# triger.net
KiCad netlist of a schematic drawn in Altium Designer
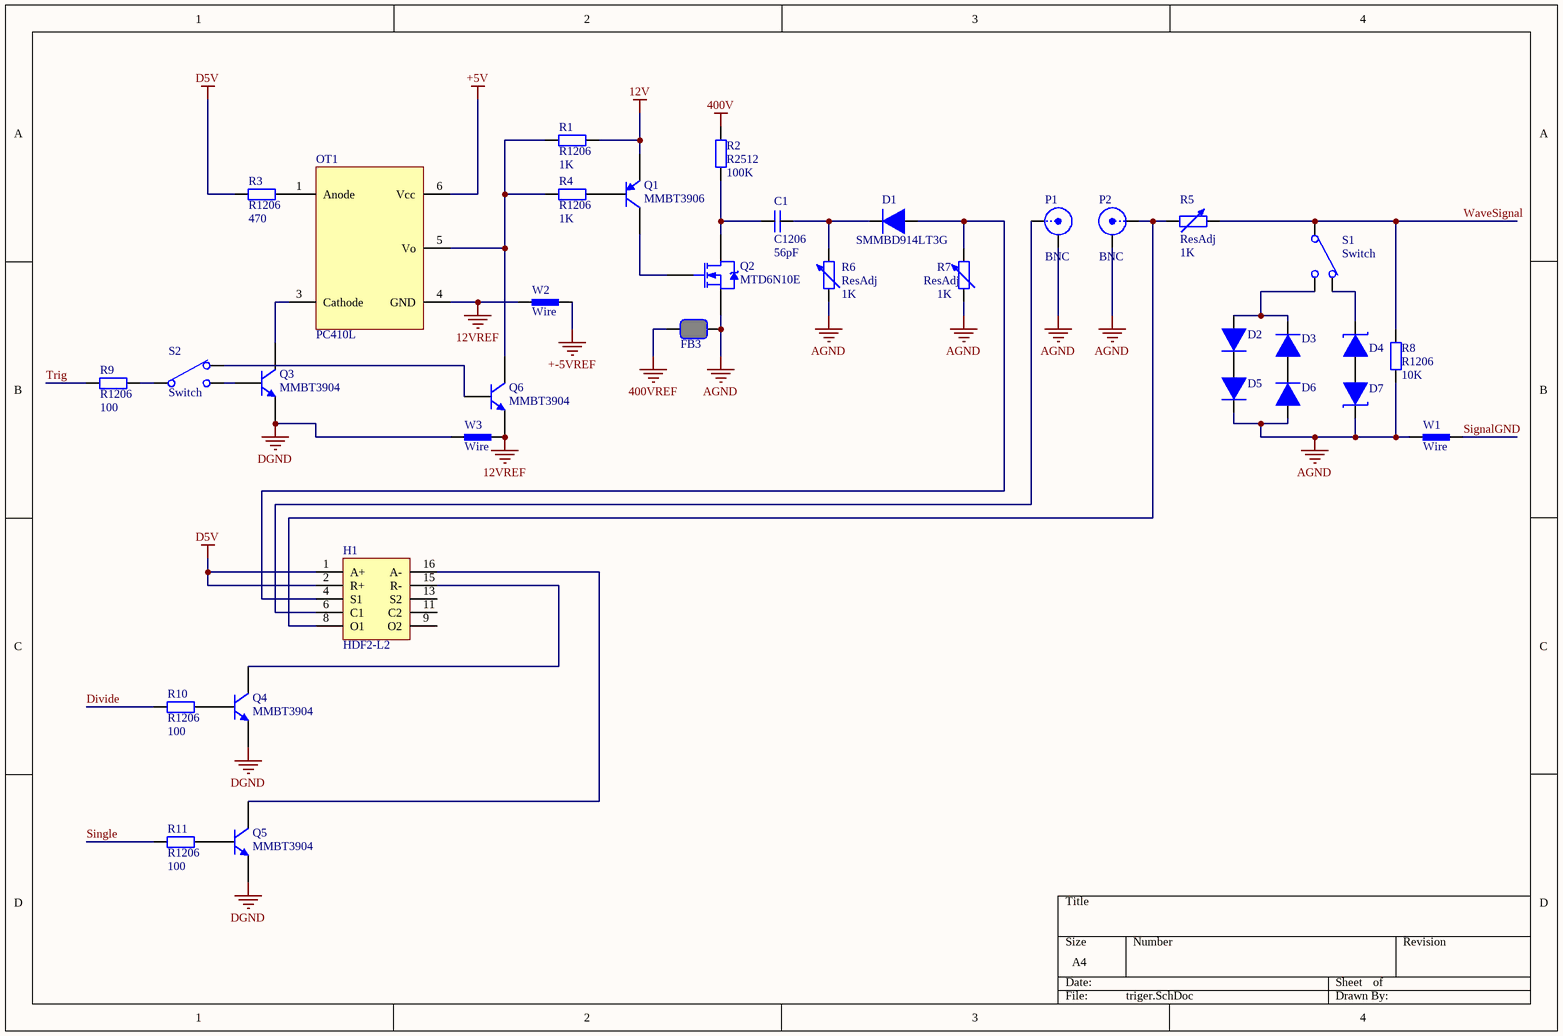
[diagram p0: triger.SchDoc]

(export (version "E")
  (design (tool "Eeschema 10.0.6"))
  (components
    (comp (ref "C1")
      (value "C1206")
      (footprint "1206")
      (description "Capacitor, 1206")
      (fields (field (name "ALTIUM_VALUE") "56pF"))
      (libsource (lib "UFDLib") (part "C1206"))
    )
    (comp (ref "D1")
      (value "SMMBD914LT3G")
      (footprint "SMMBD914LT3G")
      (description "Switching Diode")
      (libsource (lib "UFDLib") (part "SMMBD914LT3G"))
    )
    (comp (ref "D2")
      (value "SMMBD914LT3G")
      (footprint "SMMBD914LT3G")
      (description "Switching Diode")
      (libsource (lib "UFDLib") (part "SMMBD914LT3G"))
    )
    (comp (ref "D3")
      (value "SMMBD914LT3G")
      (footprint "SMMBD914LT3G")
      (description "Switching Diode")
      (libsource (lib "UFDLib") (part "SMMBD914LT3G"))
    )
    (comp (ref "D4")
      (value "ZMM2V4")
      (footprint "DIODE1206")
      (description "Voltage Stabilizing Diode, 2.4V")
      (libsource (lib "UFDLib") (part "ZMM2V4"))
    )
    (comp (ref "D5")
      (value "SMMBD914LT3G")
      (footprint "SMMBD914LT3G")
      (description "Switching Diode")
      (libsource (lib "UFDLib") (part "SMMBD914LT3G"))
    )
    (comp (ref "D6")
      (value "SMMBD914LT3G")
      (footprint "SMMBD914LT3G")
      (description "Switching Diode")
      (libsource (lib "UFDLib") (part "SMMBD914LT3G"))
    )
    (comp (ref "D7")
      (value "ZMM2V4")
      (footprint "DIODE1206")
      (description "Voltage Stabilizing Diode, 2.4V")
      (libsource (lib "UFDLib") (part "ZMM2V4"))
    )
    (comp (ref "FB3")
      (value "FB0805")
      (footprint "0805")
      (description "Chip Bead, 0805")
      (libsource (lib "UFDLib") (part "FB0805"))
    )
    (comp (ref "H1")
      (value "HDF2-L2")
      (footprint "RELAY-HFD2-L2")
      (description "Relay, HDF2-XX-XX-L2-XX")
      (libsource (lib "UFDLib") (part "Relay-HDF2-L2"))
    )
    (comp (ref "OT1") (value "PC410L") (footprint "SOP5") (libsource (lib "UFDLib") (part "PC410L")))
    (comp (ref "P1")
      (value "BNC")
      (footprint "BNC_RA CON")
      (description "BNC Elbow Connector")
      (fields (field (name "PUBLISHER") "Altium Limited"))
      (libsource (lib "Miscellaneous Connectors") (part "BNC"))
    )
    (comp (ref "P2")
      (value "BNC")
      (footprint "BNC_RA CON")
      (description "BNC Elbow Connector")
      (fields (field (name "PUBLISHER") "Altium Limited"))
      (libsource (lib "Miscellaneous Connectors") (part "BNC"))
    )
    (comp (ref "Q1")
      (value "MMBT3906")
      (footprint "SOT23_M")
      (description "PNP Switching Transistor")
      (fields (field (name "PUBLISHER") "Altium Limited"))
      (libsource (lib "Philips Discrete BJT - Low Power") (part "MMBT3906"))
    )
    (comp (ref "Q2")
      (value "MTD6N10E")
      (footprint "369A-13")
      (description "TMOS E-FET Power Field Effect Transistor DPAK for Surface Mount")
      (fields (field (name "PUBLISHER") "Altium Limited"))
      (libsource (lib "Motorola Discrete MOSFET") (part "MTD6N10E"))
    )
    (comp (ref "Q3")
      (value "MMBT3904")
      (footprint "SOT23_M")
      (description "NPN Switching Transistor")
      (fields (field (name "PUBLISHER") "Altium Limited"))
      (libsource (lib "Philips Discrete BJT - Low Power") (part "MMBT3904"))
    )
    (comp (ref "Q4")
      (value "MMBT3904")
      (footprint "SOT23_M")
      (description "NPN Switching Transistor")
      (fields (field (name "PUBLISHER") "Altium Limited"))
      (libsource (lib "Philips Discrete BJT - Low Power") (part "MMBT3904"))
    )
    (comp (ref "Q5")
      (value "MMBT3904")
      (footprint "SOT23_M")
      (description "NPN Switching Transistor")
      (fields (field (name "PUBLISHER") "Altium Limited"))
      (libsource (lib "Philips Discrete BJT - Low Power") (part "MMBT3904"))
    )
    (comp (ref "Q6")
      (value "MMBT3904")
      (footprint "SOT23_M")
      (description "NPN Switching Transistor")
      (fields (field (name "PUBLISHER") "Altium Limited"))
      (libsource (lib "Philips Discrete BJT - Low Power") (part "MMBT3904"))
    )
    (comp (ref "R1")
      (value "R1206")
      (footprint "1206")
      (description "Resistor, 1206, 1/4W")
      (fields (field (name "ALTIUM_VALUE") "1K"))
      (libsource (lib "UFDLib") (part "R1206"))
    )
    (comp (ref "R2")
      (value "R2512")
      (footprint "2512")
      (description "Resistor, 2512, 1W")
      (fields (field (name "ALTIUM_VALUE") "100K"))
      (libsource (lib "UFDLib") (part "R2512"))
    )
    (comp (ref "R3")
      (value "R1206")
      (footprint "1206")
      (description "Resistor, 1206, 1/4W")
      (fields (field (name "ALTIUM_VALUE") "470"))
      (libsource (lib "UFDLib") (part "R1206"))
    )
    (comp (ref "R4")
      (value "R1206")
      (footprint "1206")
      (description "Resistor, 1206, 1/4W")
      (fields (field (name "ALTIUM_VALUE") "1K"))
      (libsource (lib "UFDLib") (part "R1206"))
    )
    (comp (ref "R5")
      (value "ResAdj")
      (footprint "Adjust Resistor")
      (description "Adjustable Resistor")
      (fields (field (name "ALTIUM_VALUE") "1K"))
      (libsource (lib "UFDLib") (part "ResAdj"))
    )
    (comp (ref "R6")
      (value "ResAdj")
      (footprint "Adjust Resistor")
      (description "Adjustable Resistor")
      (fields (field (name "ALTIUM_VALUE") "1K"))
      (libsource (lib "") (part "ResAdj_1"))
    )
    (comp (ref "R7")
      (value "ResAdj")
      (footprint "Adjust Resistor")
      (description "Adjustable Resistor")
      (fields (field (name "ALTIUM_VALUE") "1K"))
      (libsource (lib "") (part "ResAdj_1"))
    )
    (comp (ref "R8")
      (value "R1206")
      (footprint "1206")
      (description "Resistor, 1206, 1/4W")
      (fields (field (name "ALTIUM_VALUE") "10K"))
      (libsource (lib "") (part "R1206_1"))
    )
    (comp (ref "R9")
      (value "R1206")
      (footprint "1206")
      (description "Resistor, 1206, 1/4W")
      (fields (field (name "ALTIUM_VALUE") "100"))
      (libsource (lib "UFDLib") (part "R1206"))
    )
    (comp (ref "R10")
      (value "R1206")
      (footprint "1206")
      (description "Resistor, 1206, 1/4W")
      (fields (field (name "ALTIUM_VALUE") "100"))
      (libsource (lib "UFDLib") (part "R1206"))
    )
    (comp (ref "R11")
      (value "R1206")
      (footprint "1206")
      (description "Resistor, 1206, 1/4W")
      (fields (field (name "ALTIUM_VALUE") "100"))
      (libsource (lib "UFDLib") (part "R1206"))
    )
    (comp (ref "S1")
      (value "Switch")
      (footprint "MSS-22C02")
      (description "Duble Switch")
      (libsource (lib "UFDLib") (part "MSS-22C02"))
    )
    (comp (ref "S2")
      (value "Switch")
      (footprint "MSS-22C02")
      (description "Duble Switch")
      (libsource (lib "UFDLib") (part "MSS-22C02"))
    )
    (comp (ref "W1") (value "Wire") (footprint "WIRE") (libsource (lib "UFDLib") (part "Wire")))
    (comp (ref "W2") (value "Wire") (footprint "WIRE") (libsource (lib "UFDLib") (part "Wire")))
    (comp (ref "W3") (value "Wire") (footprint "WIRE") (libsource (lib "UFDLib") (part "Wire")))
  )
  (nets
    (net (code "1") (name "+-5VREF") (class "Default")
      (node (ref "W2") (pin "2") (pinfunction "b_2") (pintype "passive"))
    )
    (net (code "2") (name "+5V") (class "Default")
      (node (ref "OT1") (pin "6") (pinfunction "Vcc_6") (pintype "passive"))
    )
    (net (code "3") (name "/Divide") (class "Default")
      (node (ref "R10") (pin "1") (pinfunction "a_1") (pintype "passive"))
    )
    (net (code "4") (name "/SignalGND") (class "Default")
      (node (ref "W1") (pin "2") (pinfunction "b_2") (pintype "passive"))
    )
    (net (code "5") (name "/Single") (class "Default")
      (node (ref "R11") (pin "1") (pinfunction "a_1") (pintype "passive"))
    )
    (net (code "6") (name "/Trig") (class "Default")
      (node (ref "R9") (pin "1") (pinfunction "a_1") (pintype "passive"))
    )
    (net (code "7") (name "/WaveSignal") (class "Default")
      (node (ref "R5") (pin "b") (pinfunction "b_b") (pintype "passive"))
      (node (ref "R8") (pin "2") (pinfunction "b_2") (pintype "passive"))
      (node (ref "S1") (pin "a") (pinfunction "a_a") (pintype "passive"))
    )
    (net (code "8") (name "12V") (class "Default")
      (node (ref "Q1") (pin "2") (pinfunction "E_2") (pintype "passive"))
      (node (ref "R1") (pin "2") (pinfunction "b_2") (pintype "passive"))
    )
    (net (code "9") (name "12VREF") (class "Default")
      (node (ref "OT1") (pin "4") (pinfunction "GND_4") (pintype "passive"))
      (node (ref "Q6") (pin "2") (pinfunction "E_2") (pintype "passive"))
      (node (ref "W2") (pin "1") (pinfunction "a_1") (pintype "passive"))
      (node (ref "W3") (pin "2") (pinfunction "b_2") (pintype "passive"))
    )
    (net (code "10") (name "400V") (class "Default")
      (node (ref "R2") (pin "2") (pinfunction "b_2") (pintype "passive"))
    )
    (net (code "11") (name "400VREF") (class "Default")
      (node (ref "FB3") (pin "2") (pinfunction "b_2") (pintype "passive"))
    )
    (net (code "12") (name "AGND") (class "Default")
      (node (ref "D5") (pin "3") (pinfunction "c_3") (pintype "passive"))
      (node (ref "D6") (pin "1") (pinfunction "a_1") (pintype "passive"))
      (node (ref "D7") (pin "2") (pinfunction "b_2") (pintype "passive"))
      (node (ref "FB3") (pin "1") (pinfunction "a_1") (pintype "passive"))
      (node (ref "P1") (pin "2") (pinfunction "Y_2") (pintype "passive"))
      (node (ref "P2") (pin "2") (pinfunction "Y_2") (pintype "passive"))
      (node (ref "Q2") (pin "3") (pinfunction "S_3") (pintype "passive"))
      (node (ref "R6") (pin "a") (pinfunction "a_a") (pintype "passive"))
      (node (ref "R7") (pin "a") (pinfunction "a_a") (pintype "passive"))
      (node (ref "R8") (pin "1") (pinfunction "a_1") (pintype "passive"))
      (node (ref "W1") (pin "1") (pinfunction "a_1") (pintype "passive"))
    )
    (net (code "13") (name "D5V") (class "Default")
      (node (ref "H1") (pin "1") (pinfunction "A+_1") (pintype "passive"))
      (node (ref "H1") (pin "2") (pinfunction "R+_2") (pintype "passive"))
      (node (ref "R3") (pin "1") (pinfunction "a_1") (pintype "passive"))
    )
    (net (code "14") (name "DGND") (class "Default")
      (node (ref "Q3") (pin "2") (pinfunction "E_2") (pintype "passive"))
      (node (ref "Q4") (pin "2") (pinfunction "E_2") (pintype "passive"))
      (node (ref "Q5") (pin "2") (pinfunction "E_2") (pintype "passive"))
      (node (ref "W3") (pin "1") (pinfunction "a_1") (pintype "passive"))
    )
    (net (code "15") (name "Net-(C1-a)") (class "Default")
      (node (ref "C1") (pin "1") (pinfunction "a_1") (pintype "passive"))
      (node (ref "Q2") (pin "4") (pinfunction "D_4") (pintype "passive"))
      (node (ref "R2") (pin "1") (pinfunction "a_1") (pintype "passive"))
    )
    (net (code "16") (name "Net-(C1-b)") (class "Default")
      (node (ref "C1") (pin "2") (pinfunction "b_2") (pintype "passive"))
      (node (ref "D1") (pin "3") (pinfunction "c_3") (pintype "passive"))
      (node (ref "R6") (pin "b") (pinfunction "b_b") (pintype "passive"))
    )
    (net (code "17") (name "Net-(D1-a)") (class "Default")
      (node (ref "D1") (pin "1") (pinfunction "a_1") (pintype "passive"))
      (node (ref "H1") (pin "4") (pinfunction "S1_4") (pintype "passive"))
      (node (ref "R7") (pin "b") (pinfunction "b_b") (pintype "passive"))
    )
    (net (code "18") (name "Net-(D2-a)") (class "Default")
      (node (ref "D2") (pin "1") (pinfunction "a_1") (pintype "passive"))
      (node (ref "D3") (pin "3") (pinfunction "c_3") (pintype "passive"))
      (node (ref "S1") (pin "c") (pinfunction "c_c") (pintype "passive"))
    )
    (net (code "19") (name "Net-(D2-c)") (class "Default")
      (node (ref "D2") (pin "3") (pinfunction "c_3") (pintype "passive"))
      (node (ref "D5") (pin "1") (pinfunction "a_1") (pintype "passive"))
    )
    (net (code "20") (name "Net-(D3-a)") (class "Default")
      (node (ref "D3") (pin "1") (pinfunction "a_1") (pintype "passive"))
      (node (ref "D6") (pin "3") (pinfunction "c_3") (pintype "passive"))
    )
    (net (code "21") (name "Net-(D4-a)") (class "Default")
      (node (ref "D4") (pin "1") (pinfunction "a_1") (pintype "passive"))
      (node (ref "D7") (pin "1") (pinfunction "a_1") (pintype "passive"))
    )
    (net (code "22") (name "Net-(D4-b)") (class "Default")
      (node (ref "D4") (pin "2") (pinfunction "b_2") (pintype "passive"))
      (node (ref "S1") (pin "b") (pinfunction "b_b") (pintype "passive"))
    )
    (net (code "23") (name "Net-(H1-A-)") (class "Default")
      (node (ref "H1") (pin "16") (pinfunction "A-_16") (pintype "passive"))
      (node (ref "Q5") (pin "3") (pinfunction "C_3") (pintype "passive"))
    )
    (net (code "24") (name "Net-(H1-C1)") (class "Default")
      (node (ref "H1") (pin "6") (pinfunction "C1_6") (pintype "passive"))
      (node (ref "P1") (pin "1") (pinfunction "X_1") (pintype "passive"))
    )
    (net (code "25") (name "Net-(H1-O1)") (class "Default")
      (node (ref "H1") (pin "8") (pinfunction "O1_8") (pintype "passive"))
      (node (ref "P2") (pin "1") (pinfunction "X_1") (pintype "passive"))
      (node (ref "R5") (pin "a") (pinfunction "a_a") (pintype "passive"))
    )
    (net (code "26") (name "Net-(H1-R-)") (class "Default")
      (node (ref "H1") (pin "15") (pinfunction "R-_15") (pintype "passive"))
      (node (ref "Q4") (pin "3") (pinfunction "C_3") (pintype "passive"))
    )
    (net (code "27") (name "Net-(OT1-Anode)") (class "Default")
      (node (ref "OT1") (pin "1") (pinfunction "Anode_1") (pintype "passive"))
      (node (ref "R3") (pin "2") (pinfunction "b_2") (pintype "passive"))
    )
    (net (code "28") (name "Net-(OT1-Cathode)") (class "Default")
      (node (ref "OT1") (pin "3") (pinfunction "Cathode_3") (pintype "passive"))
      (node (ref "Q3") (pin "3") (pinfunction "C_3") (pintype "passive"))
    )
    (net (code "29") (name "Net-(OT1-Vo)") (class "Default")
      (node (ref "OT1") (pin "5") (pinfunction "Vo_5") (pintype "passive"))
      (node (ref "Q6") (pin "3") (pinfunction "C_3") (pintype "passive"))
      (node (ref "R1") (pin "1") (pinfunction "a_1") (pintype "passive"))
      (node (ref "R4") (pin "1") (pinfunction "a_1") (pintype "passive"))
    )
    (net (code "30") (name "Net-(Q1-B)") (class "Default")
      (node (ref "Q1") (pin "1") (pinfunction "B_1") (pintype "passive"))
      (node (ref "R4") (pin "2") (pinfunction "b_2") (pintype "passive"))
    )
    (net (code "31") (name "Net-(Q1-C)") (class "Default")
      (node (ref "Q1") (pin "3") (pinfunction "C_3") (pintype "passive"))
      (node (ref "Q2") (pin "1") (pinfunction "G_1") (pintype "passive"))
    )
    (net (code "32") (name "Net-(Q3-B)") (class "Default")
      (node (ref "Q3") (pin "1") (pinfunction "B_1") (pintype "passive"))
      (node (ref "S2") (pin "c") (pinfunction "c_c") (pintype "passive"))
    )
    (net (code "33") (name "Net-(Q4-B)") (class "Default")
      (node (ref "Q4") (pin "1") (pinfunction "B_1") (pintype "passive"))
      (node (ref "R10") (pin "2") (pinfunction "b_2") (pintype "passive"))
    )
    (net (code "34") (name "Net-(Q5-B)") (class "Default")
      (node (ref "Q5") (pin "1") (pinfunction "B_1") (pintype "passive"))
      (node (ref "R11") (pin "2") (pinfunction "b_2") (pintype "passive"))
    )
    (net (code "35") (name "Net-(Q6-B)") (class "Default")
      (node (ref "Q6") (pin "1") (pinfunction "B_1") (pintype "passive"))
      (node (ref "S2") (pin "b") (pinfunction "b_b") (pintype "passive"))
    )
    (net (code "36") (name "Net-(R9-b)") (class "Default")
      (node (ref "R9") (pin "2") (pinfunction "b_2") (pintype "passive"))
      (node (ref "S2") (pin "a") (pinfunction "a_a") (pintype "passive"))
    )
    (net (code "37") (name "unconnected-(H1-C2-Pad11)") (class "Default")
      (node (ref "H1") (pin "11") (pinfunction "C2_11") (pintype "passive"))
    )
    (net (code "38") (name "unconnected-(H1-O2-Pad9)") (class "Default")
      (node (ref "H1") (pin "9") (pinfunction "O2_9") (pintype "passive"))
    )
    (net (code "39") (name "unconnected-(H1-S2-Pad13)") (class "Default")
      (node (ref "H1") (pin "13") (pinfunction "S2_13") (pintype "passive"))
    )
  )
)
